# LED_Driver.net
KiCad netlist of a schematic drawn in Altium Designer
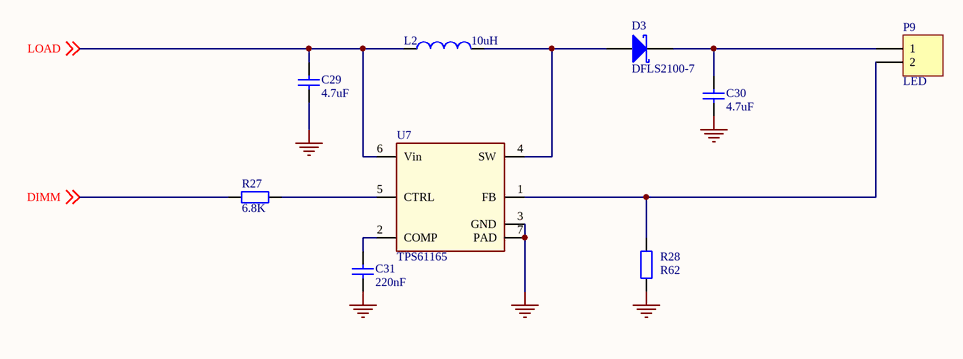
[diagram p0: LED Driver.SchDoc]

(export (version "E")
  (design (tool "Eeschema 10.0.6"))
  (components
    (comp (ref "C29")
      (value "4.7uF")
      (footprint "C0805")
      (description "Capacitor ceramic")
      (fields
        (field (name "MANUFACTURER") "Murata Electronics")
        (field (name "MANUFACTURER PART NO.") "GRM219R6YA475KA73D")
      )
      (libsource (lib "Miscellaneous Devices") (part "Cap"))
    )
    (comp (ref "C30")
      (value "4.7uF")
      (footprint "C0805")
      (description "Capacitor ceramic")
      (fields
        (field (name "MANUFACTURER") "Murata Electronics")
        (field (name "MANUFACTURER PART NO.") "GRM219R6YA475KA73D")
      )
      (libsource (lib "Miscellaneous Devices") (part "Cap"))
    )
    (comp (ref "C31")
      (value "220nF")
      (footprint "C0402")
      (description "Capacitor ceramic")
      (fields
        (field (name "MANUFACTURER") "Yageo")
        (field (name "MANUFACTURER PART NO.") "CC0402KRX5R8BB224")
      )
      (libsource (lib "Miscellaneous Devices") (part "Cap"))
    )
    (comp (ref "D3")
      (value "DFLS2100-7")
      (footprint "PowerDI123")
      (description "Schottky Diode")
      (fields (field (name "MANUFACTURER") "Diodes Incorporated"))
      (libsource (lib "Miscellaneous Devices") (part "D Schottky"))
    )
    (comp (ref "L2")
      (value "10uH")
      (footprint "LQH3NP")
      (description "Inductor")
      (fields
        (field (name "MANUFACTURER") "Murata Electronics")
        (field (name "MANUFACTURER PART NO.") "LQH3NPN100MMEL")
      )
      (libsource (lib "Miscellaneous Devices") (part "Inductor"))
    )
    (comp (ref "P9")
      (value "LED")
      (footprint "TERM2pin5mm")
      (description "Header, 2-Pin")
      (fields (field (name "MANUFACTURER") "SAURO") (field (name "MANUFACTURER PART NO.") "MSG02001"))
      (libsource (lib "Miscellaneous Connectors") (part "Header 2"))
    )
    (comp (ref "R27")
      (value "6.8K")
      (footprint "R0402")
      (description "Resistor")
      (fields (field (name "MANUFACTURER") "Yageo") (field (name "MANUFACTURER PART NO.") "RC0402JR-076K8L"))
      (libsource (lib "Miscellaneous Devices") (part "Res2"))
    )
    (comp (ref "R28")
      (value "R62")
      (footprint "R1206")
      (description "Resistor")
      (fields
        (field (name "MANUFACTURER") "Panasonic Electronic Components")
        (field (name "MANUFACTURER PART NO.") "ERJ-8RQFR62V")
      )
      (libsource (lib "") (part "Res2_1"))
    )
    (comp (ref "U7")
      (value "TPS61165")
      (footprint "QFN-6_custom")
      (description "HBLED Driver")
      (fields (field (name "MANUFACTURER") "TI") (field (name "MANUFACTURER PART NO.") "TPS61165DRVT"))
      (libsource (lib "Solar_LED_project") (part "TPS61165"))
    )
  )
  (nets
    (net (code "1") (name "DIMM") (class "Default")
      (node (ref "R27") (pin "1") (pinfunction "1_1") (pintype "passive"))
    )
    (net (code "2") (name "GND") (class "Default")
      (node (ref "C29") (pin "2") (pinfunction "2_2") (pintype "passive"))
      (node (ref "C30") (pin "2") (pinfunction "2_2") (pintype "passive"))
      (node (ref "C31") (pin "2") (pinfunction "2_2") (pintype "passive"))
      (node (ref "R28") (pin "1") (pinfunction "1_1") (pintype "passive"))
      (node (ref "U7") (pin "3") (pinfunction "GND_3") (pintype "passive"))
      (node (ref "U7") (pin "7") (pinfunction "PAD_7") (pintype "passive"))
    )
    (net (code "3") (name "LOAD") (class "Default")
      (node (ref "C29") (pin "1") (pinfunction "1_1") (pintype "passive"))
      (node (ref "L2") (pin "1") (pinfunction "1_1") (pintype "passive"))
      (node (ref "U7") (pin "6") (pinfunction "Vin_6") (pintype "passive"))
    )
    (net (code "4") (name "Net-(D3-A)") (class "Default")
      (node (ref "D3") (pin "1") (pinfunction "A_1") (pintype "passive"))
      (node (ref "L2") (pin "2") (pinfunction "2_2") (pintype "passive"))
      (node (ref "U7") (pin "4") (pinfunction "SW_4") (pintype "passive"))
    )
    (net (code "5") (name "Net-(D3-K)") (class "Default")
      (node (ref "C30") (pin "1") (pinfunction "1_1") (pintype "passive"))
      (node (ref "D3") (pin "2") (pinfunction "K_2") (pintype "passive"))
      (node (ref "P9") (pin "1") (pinfunction "1_1") (pintype "passive"))
    )
    (net (code "6") (name "Net-(U7-COMP)") (class "Default")
      (node (ref "C31") (pin "1") (pinfunction "1_1") (pintype "passive"))
      (node (ref "U7") (pin "2") (pinfunction "COMP_2") (pintype "passive"))
    )
    (net (code "7") (name "Net-(U7-CTRL)") (class "Default")
      (node (ref "R27") (pin "2") (pinfunction "2_2") (pintype "passive"))
      (node (ref "U7") (pin "5") (pinfunction "CTRL_5") (pintype "passive"))
    )
    (net (code "8") (name "Net-(U7-FB)") (class "Default")
      (node (ref "P9") (pin "2") (pinfunction "2_2") (pintype "passive"))
      (node (ref "R28") (pin "2") (pinfunction "2_2") (pintype "passive"))
      (node (ref "U7") (pin "1") (pinfunction "FB_1") (pintype "passive"))
    )
  )
)
